# max486x.net
KiCad netlist of a schematic drawn in EAGLE
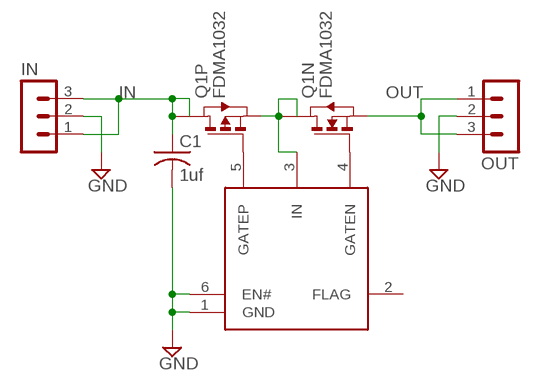
[diagram p0: schematic, sheet 1]

(export (version "E")
  (design (tool "Eeschema 10.0.6"))
  (components
    (comp (ref "C1")
      (value "1uf")
      (footprint "eagle-import:C1206")
      (libsource (lib "eagle-import") (part "C-USC1206"))
    )
    (comp (ref "IC1")
      (value "MAX486X")
      (footprint "eagle-import:L622")
      (libsource (lib "eagle-import") (part "MAX486X"))
    )
    (comp (ref "IN")
      (value "MA03-1")
      (footprint "eagle-import:MA03-1")
      (libsource (lib "eagle-import") (part "MA03-1"))
    )
    (comp (ref "OUT")
      (value "MA03-1")
      (footprint "eagle-import:MA03-1")
      (libsource (lib "eagle-import") (part "MA03-1"))
    )
    (comp (ref "Q1")
      (value "FDMA1032")
      (footprint "eagle-import:MLP06")
      (libsource (lib "eagle-import") (part "FDMA1032"))
    )
  )
  (nets
    (net (code "1") (name "/IN") (class "Default")
      (node (ref "C1") (pin "1") (pinfunction "1_1") (pintype "passive"))
      (node (ref "IN") (pin "1") (pinfunction "1_1") (pintype "passive"))
      (node (ref "IN") (pin "3") (pinfunction "3_3") (pintype "passive"))
      (node (ref "Q1") (pin "3") (pinfunction "D1_3") (pintype "passive"))
      (node (ref "Q1") (pin "3@1") (pinfunction "D_3@1") (pintype "passive"))
    )
    (net (code "2") (name "/OUT") (class "Default")
      (node (ref "OUT") (pin "1") (pinfunction "1_1") (pintype "passive"))
      (node (ref "OUT") (pin "3") (pinfunction "3_3") (pintype "passive"))
      (node (ref "Q1") (pin "1") (pinfunction "S_1") (pintype "passive"))
    )
    (net (code "3") (name "GND") (class "Default")
      (node (ref "C1") (pin "2") (pinfunction "2_2") (pintype "passive"))
      (node (ref "IC1") (pin "1") (pinfunction "GND_1") (pintype "power_in"))
      (node (ref "IC1") (pin "6") (pinfunction "EN#_6") (pintype "input"))
      (node (ref "IN") (pin "2") (pinfunction "2_2") (pintype "passive"))
      (node (ref "OUT") (pin "2") (pinfunction "2_2") (pintype "passive"))
    )
    (net (code "4") (name "Net-(IC1-GATEN)") (class "Default")
      (node (ref "IC1") (pin "4") (pinfunction "GATEN_4") (pintype "output"))
      (node (ref "Q1") (pin "2") (pinfunction "G_2") (pintype "passive"))
    )
    (net (code "5") (name "Net-(IC1-GATEP)") (class "Default")
      (node (ref "IC1") (pin "5") (pinfunction "GATEP_5") (pintype "output"))
      (node (ref "Q1") (pin "5") (pinfunction "G_5") (pintype "passive"))
    )
    (net (code "6") (name "Net-(IC1-IN)") (class "Default")
      (node (ref "IC1") (pin "3") (pinfunction "IN_3") (pintype "input"))
      (node (ref "Q1") (pin "4") (pinfunction "S_4") (pintype "passive"))
      (node (ref "Q1") (pin "6") (pinfunction "D_6") (pintype "passive"))
      (node (ref "Q1") (pin "6@1") (pinfunction "D1_6@1") (pintype "passive"))
    )
    (net (code "7") (name "unconnected-(IC1-FLAG-Pad2)") (class "Default")
      (node (ref "IC1") (pin "2") (pinfunction "FLAG_2") (pintype "open_collector"))
    )
  )
)
